# Mynd_UI.net
KiCad netlist of a schematic drawn in Altium Designer
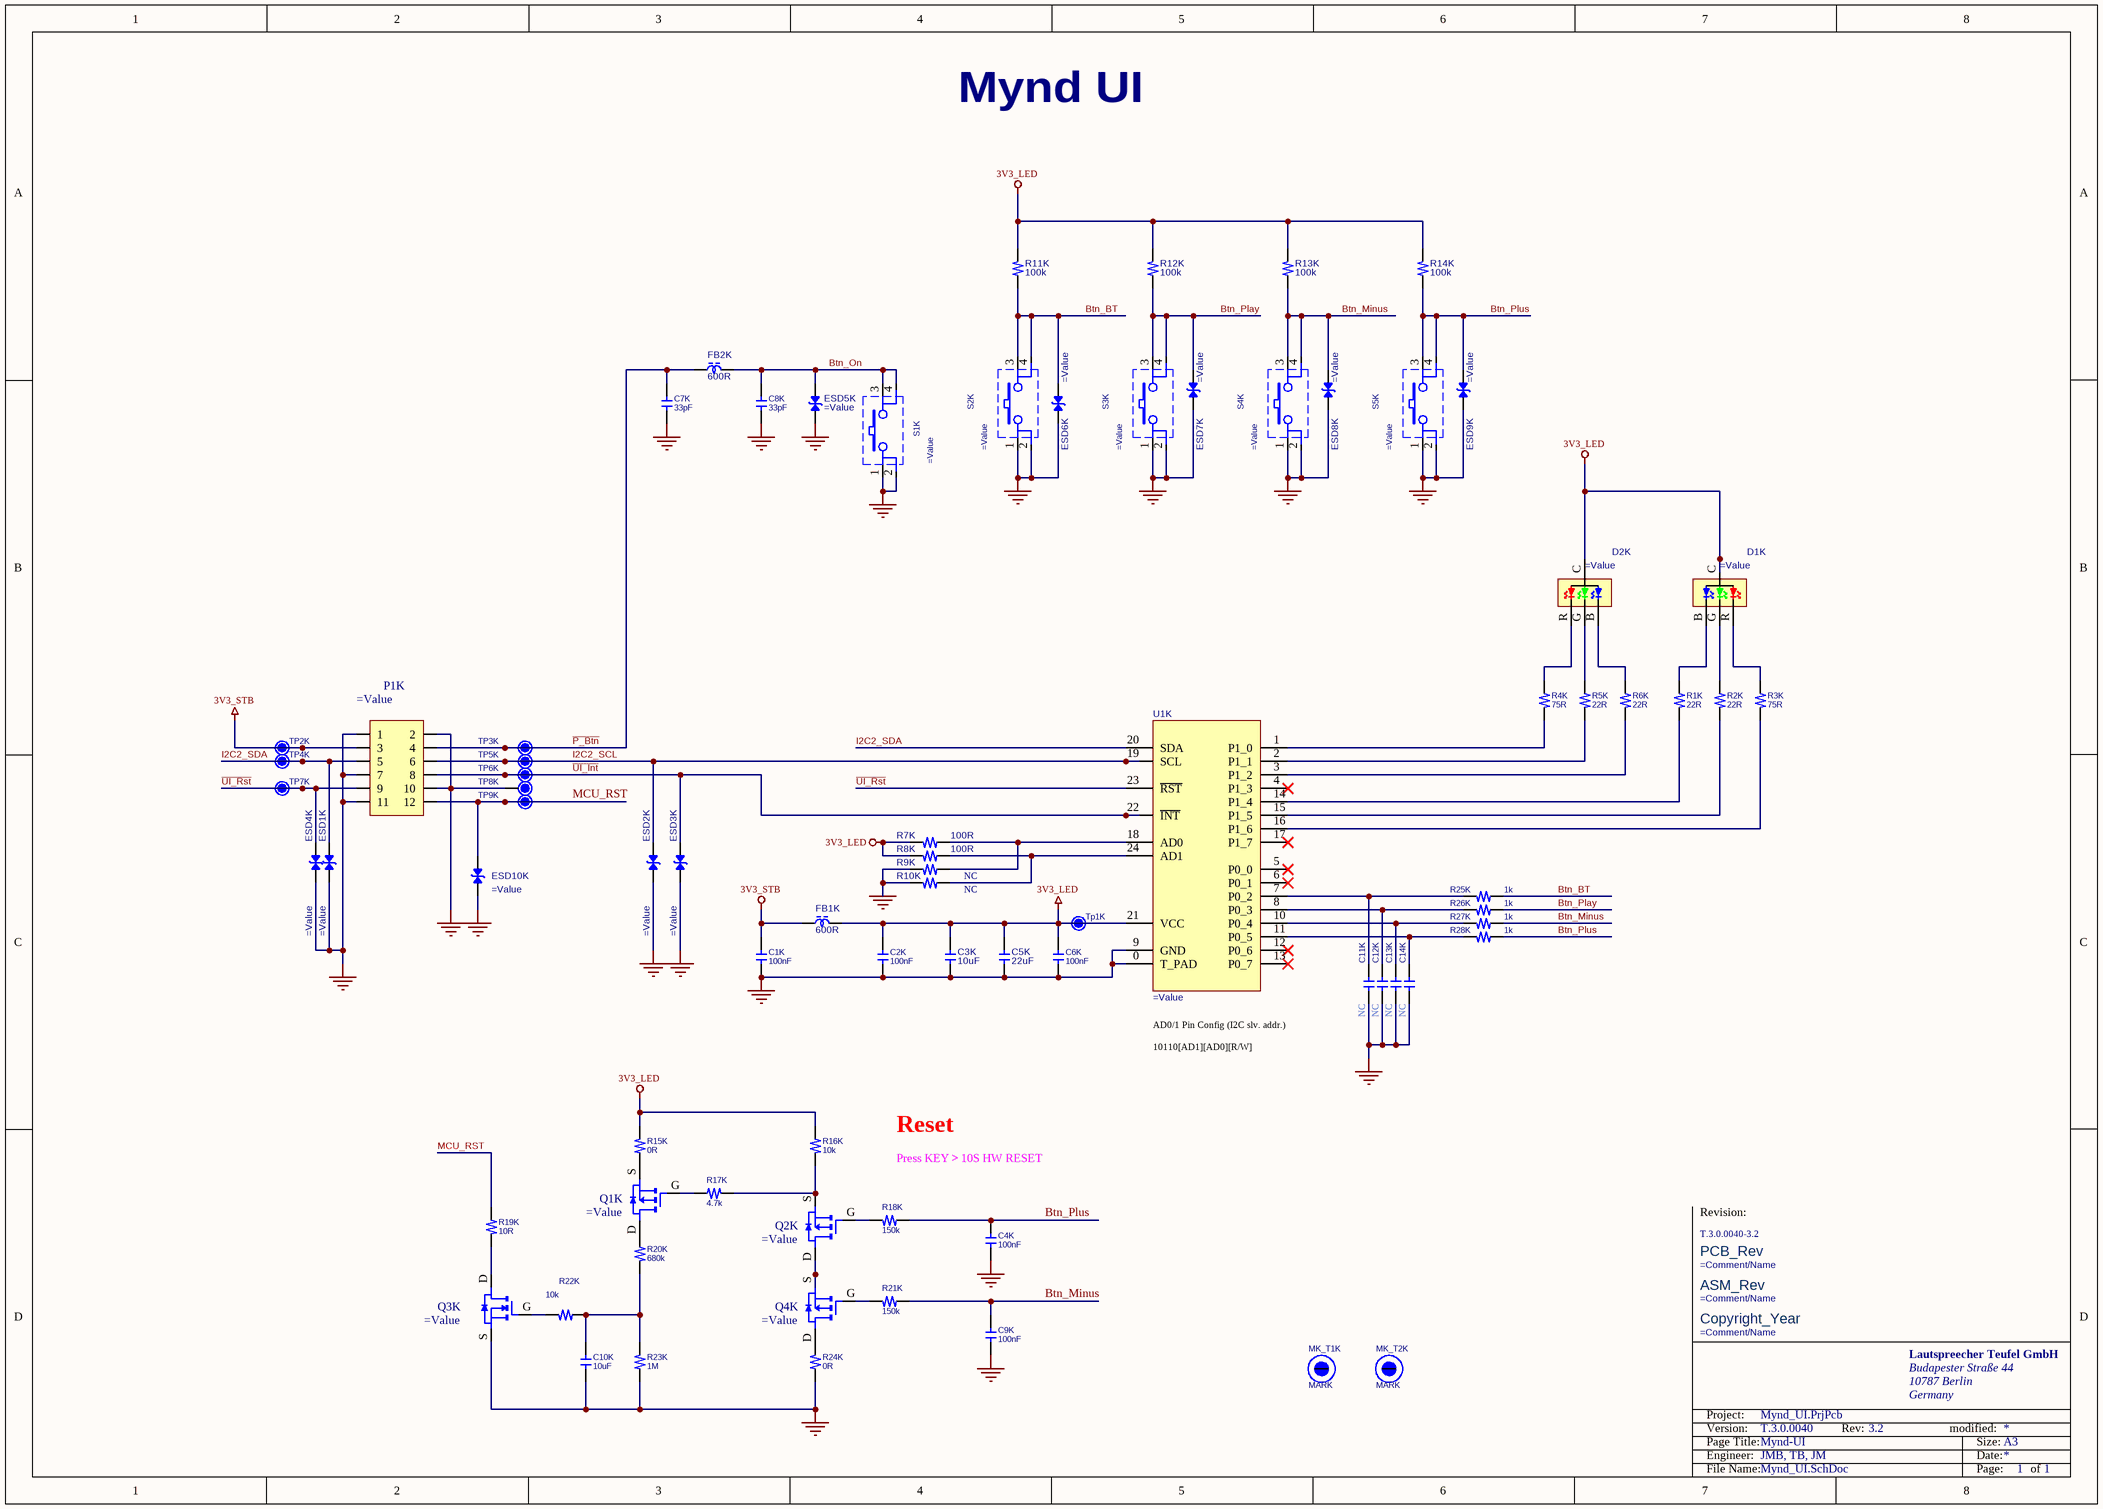
[diagram p0: Mynd_UI.SchDoc]

(export (version "E")
  (design (tool "Eeschema 10.0.6"))
  (components
    (comp (ref "C1K")
      (value "100nF")
      (footprint "C0603X100")
      (description "GPHF SMD M CAP 100nF 16V ±10%  0603 X7R")
      (fields (field (name "MANUFACTURER") "Multi-Sourced") (field (name "TOLERANCE") "±10%"))
      (libsource (lib "altium-import") (part "root_3_CAP1_"))
    )
    (comp (ref "C2K")
      (value "100nF")
      (footprint "C0603X100")
      (description "GPHF SMD M CAP 100nF 16V ±10%  0603 X7R")
      (fields (field (name "MANUFACTURER") "Multi-Sourced") (field (name "TOLERANCE") "±10%"))
      (libsource (lib "altium-import") (part "root_3_CAP1_"))
    )
    (comp (ref "C3K")
      (value "10uF")
      (footprint "C0805_145")
      (description "PSHF SMD M CAP 10uF 16V ±10% 0805 X7R")
      (fields (field (name "MANUFACTURER") "Multi-Sourced") (field (name "TOLERANCE") "±10% 0805"))
      (libsource (lib "altium-import") (part "root_3_CAP1_"))
    )
    (comp (ref "C4K")
      (value "100nF")
      (footprint "C0603X100")
      (description "GPHF SMD M CAP 100nF 16V ±10%  0603 X7R")
      (fields (field (name "MANUFACTURER") "Multi-Sourced") (field (name "VOLTAGE") "16V"))
      (libsource (lib "altium-import") (part "root_3_mirrored_CAP1_"))
    )
    (comp (ref "C5K")
      (value "22uF")
      (footprint "C1206")
      (description "PSHF SMD M CAP 22uF 16V ±10% 1206 X5R")
      (fields (field (name "MANUFACTURER") "Multi-Sourced") (field (name "TOLERANCE") "±10%"))
      (libsource (lib "altium-import") (part "root_1_mirrored_CAP1_"))
    )
    (comp (ref "C6K")
      (value "100nF")
      (footprint "C0603X100")
      (description "GPHF SMD M CAP 100nF 16V ±10%  0603 X7R")
      (fields (field (name "MANUFACTURER") "Multi-Sourced") (field (name "TOLERANCE") "±10%"))
      (libsource (lib "altium-import") (part "root_1_CAP1_"))
    )
    (comp (ref "C7K")
      (value "33pF")
      (footprint "C0603X80")
      (description "PSHF SMD M CAP 33pF 50V ±5% 0603 NPO")
      (fields (field (name "MANUFACTURER") "Multi-Sourced") (field (name "TOLERANCE") "±5%"))
      (libsource (lib "altium-import") (part "root_3_CAP1_"))
    )
    (comp (ref "C8K")
      (value "33pF")
      (footprint "C0603X80")
      (description "PSHF SMD M CAP 33pF 50V ±5% 0603 NPO")
      (fields (field (name "MANUFACTURER") "Multi-Sourced") (field (name "TOLERANCE") "±5%"))
      (libsource (lib "altium-import") (part "root_3_CAP1_"))
    )
    (comp (ref "C9K")
      (value "100nF")
      (footprint "C0603X100")
      (description "GPHF SMD M CAP 100nF 16V ±10%  0603 X7R")
      (fields (field (name "MANUFACTURER") "Multi-Sourced") (field (name "VOLTAGE") "16V"))
      (libsource (lib "altium-import") (part "root_3_mirrored_CAP1_"))
    )
    (comp (ref "C10K")
      (value "10uF")
      (footprint "C0805_145")
      (description "PSHF SMD M CAP 10uF 10V ±10% 0805 X5R")
      (fields (field (name "MANUFACTURER") "Multi-Sourced") (field (name "VOLTAGE") "10V"))
      (libsource (lib "altium-import") (part "root_3_mirrored_CAP1_"))
    )
    (comp (ref "C11K")
      (value "NC")
      (footprint "C0603X100")
      (description "GPHF SMD M CAP 100nF 16V ±10%  0603 X7R")
      (fields (field (name "MANUFACTURER") "Multi-Sourced") (field (name "TOLERANCE") "±10%"))
      (libsource (lib "altium-import") (part "root_3_CAP1_"))
    )
    (comp (ref "C12K")
      (value "NC")
      (footprint "C0603X100")
      (description "GPHF SMD M CAP 100nF 16V ±10%  0603 X7R")
      (fields (field (name "MANUFACTURER") "Multi-Sourced") (field (name "TOLERANCE") "±10%"))
      (libsource (lib "altium-import") (part "root_3_CAP1_"))
    )
    (comp (ref "C13K")
      (value "NC")
      (footprint "C0603X100")
      (description "GPHF SMD M CAP 100nF 16V ±10%  0603 X7R")
      (fields (field (name "MANUFACTURER") "Multi-Sourced") (field (name "TOLERANCE") "±10%"))
      (libsource (lib "altium-import") (part "root_3_CAP1_"))
    )
    (comp (ref "C14K")
      (value "NC")
      (footprint "C0603X100")
      (description "GPHF SMD M CAP 100nF 16V ±10%  0603 X7R")
      (fields (field (name "MANUFACTURER") "Multi-Sourced") (field (name "TOLERANCE") "±10%"))
      (libsource (lib "altium-import") (part "root_3_CAP1_"))
    )
    (comp (ref "D1K")
      (value "~")
      (footprint "LED_SMD_F_T_160X80X60")
      (description "SMD LED 4P 30mA RED&GN&BU")
      (fields (field (name "MANUFACTURER") "MINGSHUO") (field (name "PART_NUMBER") "JH-CRGBB06GTP014"))
      (libsource (lib "altium-import") (part "root_3_LED_RGB_4P_"))
    )
    (comp (ref "D2K")
      (value "~")
      (footprint "LED_SMD_F_T_160X80X60")
      (description "SMD LED 4P 30mA RED&GN&BU")
      (fields (field (name "MANUFACTURER") "MINGSHUO") (field (name "PART_NUMBER") "JH-CRGBB06GTP014"))
      (libsource (lib "altium-import") (part "root_3_mirrored_LED_RGB_4P_"))
    )
    (comp (ref "ESD1K")
      (value "~")
      (footprint "DFN2_100X60X50_65")
      (description "SMD TVS 2P 5.5 DFN1006 CESD0501CU CTE")
      (fields (field (name "MANUFACTURER") "CTE") (field (name "PART_NUMBER") "CESD0501CU"))
      (libsource (lib "altium-import") (part "root_1_DIODE_BID_ESD2_"))
    )
    (comp (ref "ESD2K")
      (value "~")
      (footprint "DFN2_100X60X50_65")
      (description "SMD TVS 2P 5.5 DFN1006 CESD0501CU CTE")
      (fields (field (name "MANUFACTURER") "CTE") (field (name "PART_NUMBER") "CESD0501CU"))
      (libsource (lib "altium-import") (part "root_1_DIODE_BID_ESD2_"))
    )
    (comp (ref "ESD3K")
      (value "~")
      (footprint "DFN2_100X60X50_65")
      (description "SMD TVS 2P 5.5 DFN1006 CESD0501CU CTE")
      (fields (field (name "MANUFACTURER") "CTE") (field (name "PART_NUMBER") "CESD0501CU"))
      (libsource (lib "altium-import") (part "root_1_DIODE_BID_ESD2_"))
    )
    (comp (ref "ESD4K")
      (value "~")
      (footprint "DFN2_100X60X50_65")
      (description "SMD TVS 2P 5.5 DFN1006 CESD0501CU CTE")
      (fields (field (name "MANUFACTURER") "CTE") (field (name "PART_NUMBER") "CESD0501CU"))
      (libsource (lib "altium-import") (part "root_1_DIODE_BID_ESD2_"))
    )
    (comp (ref "ESD5K")
      (value "~")
      (footprint "DFN2_100X60X50_65")
      (description "SMD TVS 2P DFN1006 BDFN2C121V")
      (fields (field (name "MANUFACTURER") "[]") (field (name "PART_NUMBER") "BDFN2C121V"))
      (libsource (lib "altium-import") (part "root_1_DIODE_BID_ESD2_"))
    )
    (comp (ref "ESD6K")
      (value "~")
      (footprint "DFN2_100X60X50_65")
      (description "SMD TVS 2P 5.5 DFN1006 CESD0501CU CTE")
      (fields (field (name "MANUFACTURER") "CTE") (field (name "PART_NUMBER") "CESD0501CU"))
      (libsource (lib "altium-import") (part "root_1_DIODE_BID_ESD2_"))
    )
    (comp (ref "ESD7K")
      (value "~")
      (footprint "DFN2_100X60X50_65")
      (description "SMD TVS 2P 5.5 DFN1006 CESD0501CU CTE")
      (fields (field (name "MANUFACTURER") "CTE") (field (name "PART_NUMBER") "CESD0501CU"))
      (libsource (lib "altium-import") (part "root_1_DIODE_BID_ESD2_"))
    )
    (comp (ref "ESD8K")
      (value "~")
      (footprint "DFN2_100X60X50_65")
      (description "SMD TVS 2P 5.5 DFN1006 CESD0501CU CTE")
      (fields (field (name "MANUFACTURER") "CTE") (field (name "PART_NUMBER") "CESD0501CU"))
      (libsource (lib "altium-import") (part "root_1_DIODE_BID_ESD2_"))
    )
    (comp (ref "ESD9K")
      (value "~")
      (footprint "DFN2_100X60X50_65")
      (description "SMD TVS 2P 5.5 DFN1006 CESD0501CU CTE")
      (fields (field (name "MANUFACTURER") "CTE") (field (name "PART_NUMBER") "CESD0501CU"))
      (libsource (lib "altium-import") (part "root_1_DIODE_BID_ESD2_"))
    )
    (comp (ref "ESD10K")
      (value "~")
      (footprint "DFN2_100X60X50_65")
      (description "SMD TVS 2P 5.5 DFN1006 CESD0501CU CTE")
      (fields (field (name "MANUFACTURER") "CTE") (field (name "PART_NUMBER") "CESD0501CU"))
      (libsource (lib "altium-import") (part "root_1_DIODE_BID_ESD2_"))
    )
    (comp (ref "FB1K")
      (value "600R")
      (footprint "L0603")
      (description "PS SMD FERRITE BEAD 600OHM 25% 0603")
      (fields (field (name "MANUFACTURER") "[TSA]") (field (name "TOLERANCE") "1:25%"))
      (libsource (lib "altium-import") (part "root_0_mirrored_Bead1_"))
    )
    (comp (ref "FB2K")
      (value "600R")
      (footprint "L0603")
      (description "PS SMD FERRITE BEAD 600OHM 25% 0603")
      (fields (field (name "MANUFACTURER") "[TSA]") (field (name "TOLERANCE") "1:25%"))
      (libsource (lib "altium-import") (part "root_0_Bead1_"))
    )
    (comp (ref "MK_T1K")
      (value "MARK")
      (footprint "MARK")
      (description "MARK DOT")
      (libsource (lib "altium-import") (part "root_0_MARK_"))
    )
    (comp (ref "MK_T2K")
      (value "MARK")
      (footprint "MARK")
      (description "MARK DOT")
      (libsource (lib "altium-import") (part "root_0_MARK_"))
    )
    (comp (ref "P1K")
      (value "~")
      (footprint "WB200AL_2x6P")
      (description "SMD WTB CONNECTOR 12P P2.0mm TIN")
      (fields (field (name "MANUFACTURER") "MINGHENG") (field (name "PART_NUMBER") "WB200AL-12"))
      (libsource (lib "altium-import") (part "root_0_CON 2X6P_"))
    )
    (comp (ref "Q1K")
      (value "~")
      (footprint "SOT23-GSD")
      (description "GPHF SMD FET 3P -30V SOT-23 CJ3401 CJ")
      (fields (field (name "MANUFACTURER") "CJ") (field (name "PART_NUMBER") "CJ3401"))
      (libsource (lib "altium-import") (part "root_2_P-MOS1_"))
    )
    (comp (ref "Q2K")
      (value "~")
      (footprint "SOT23-GSD")
      (description "GPHF SMD FET 3P -30V SOT-23 CJ3401 CJ")
      (fields (field (name "MANUFACTURER") "CJ") (field (name "PART_NUMBER") "CJ3401"))
      (libsource (lib "altium-import") (part "root_2_P-MOS1_"))
    )
    (comp (ref "Q3K")
      (value "~")
      (footprint "SOT23-GSD")
      (description "GP SMD FET 3P SOT23 2N7002K CTE")
      (fields (field (name "MANUFACTURER") "CTE") (field (name "PART_NUMBER") "2N7002K"))
      (libsource (lib "altium-import") (part "root_0_mirrored_N-MOS1_"))
    )
    (comp (ref "Q4K")
      (value "~")
      (footprint "SOT23-GSD")
      (description "GPHF SMD FET 3P -30V SOT-23 CJ3401 CJ")
      (fields (field (name "MANUFACTURER") "CJ") (field (name "PART_NUMBER") "CJ3401"))
      (libsource (lib "altium-import") (part "root_2_P-MOS1_"))
    )
    (comp (ref "R1K")
      (value "22R")
      (footprint "R0603")
      (description "PS SMD RES. 22OHM 1/10W 5% 0603")
      (fields (field (name "TOLERANCE") "5%") (field (name "MANUFACTURER") "Multi-Sourced"))
      (libsource (lib "altium-import") (part "root_3_mirrored_RES1_"))
    )
    (comp (ref "R2K")
      (value "22R")
      (footprint "R0603")
      (description "PS SMD RES. 22OHM 1/10W 5% 0603")
      (fields (field (name "TOLERANCE") "5%") (field (name "MANUFACTURER") "Multi-Sourced"))
      (libsource (lib "altium-import") (part "root_3_mirrored_RES1_"))
    )
    (comp (ref "R3K")
      (value "75R")
      (footprint "R0603")
      (description "PS SMD RES. 75OHM 1/10W 1% 0603")
      (fields (field (name "TOLERANCE") "1%") (field (name "MANUFACTURER") "Multi-Sourced"))
      (libsource (lib "altium-import") (part "root_3_mirrored_RES1_"))
    )
    (comp (ref "R4K")
      (value "75R")
      (footprint "R0603")
      (description "PS SMD RES. 75OHM 1/10W 1% 0603")
      (fields (field (name "TOLERANCE") "1%") (field (name "MANUFACTURER") "Multi-Sourced"))
      (libsource (lib "altium-import") (part "root_3_mirrored_RES1_"))
    )
    (comp (ref "R5K")
      (value "22R")
      (footprint "R0603")
      (description "PS SMD RES. 22OHM 1/10W 5% 0603")
      (fields (field (name "TOLERANCE") "5%") (field (name "MANUFACTURER") "Multi-Sourced"))
      (libsource (lib "altium-import") (part "root_3_mirrored_RES1_"))
    )
    (comp (ref "R6K")
      (value "22R")
      (footprint "R0603")
      (description "PS SMD RES. 22OHM 1/10W 5% 0603")
      (fields (field (name "TOLERANCE") "5%") (field (name "MANUFACTURER") "Multi-Sourced"))
      (libsource (lib "altium-import") (part "root_3_mirrored_RES1_"))
    )
    (comp (ref "R7K")
      (value "100R")
      (footprint "R0603")
      (description "PS SMD RES. 100OHM 1/10W 1% 0603")
      (fields (field (name "TOLERANCE") "1%") (field (name "MANUFACTURER") "Multi-Sourced"))
      (libsource (lib "altium-import") (part "root_0_mirrored_RES1_"))
    )
    (comp (ref "R8K")
      (value "100R")
      (footprint "R0603")
      (description "PS SMD RES. 100OHM 1/10W 1% 0603")
      (fields (field (name "TOLERANCE") "1%") (field (name "MANUFACTURER") "Multi-Sourced"))
      (libsource (lib "altium-import") (part "root_0_mirrored_RES1_"))
    )
    (comp (ref "R9K")
      (value "10k")
      (footprint "R0603")
      (description "PS SMD RES. 10KOHM 1/10W 1% 0603")
      (fields (field (name "TOLERANCE") "1%") (field (name "MANUFACTURER") "Multi-Sourced"))
      (libsource (lib "altium-import") (part "root_0_mirrored_RES1_"))
    )
    (comp (ref "R10K")
      (value "10k")
      (footprint "R0603")
      (description "PS SMD RES. 10KOHM 1/10W 1% 0603")
      (fields (field (name "TOLERANCE") "1%") (field (name "MANUFACTURER") "Multi-Sourced"))
      (libsource (lib "altium-import") (part "root_0_mirrored_RES1_"))
    )
    (comp (ref "R11K")
      (value "100k")
      (footprint "R0603")
      (description "PS SMD RES. 100KOHM 1/10W 1% 0603")
      (fields (field (name "TOLERANCE") "1%") (field (name "MANUFACTURER") "Multi-Sourced"))
      (libsource (lib "altium-import") (part "root_3_RES1_"))
    )
    (comp (ref "R12K")
      (value "100k")
      (footprint "R0603")
      (description "PS SMD RES. 100KOHM 1/10W 1% 0603")
      (fields (field (name "TOLERANCE") "1%") (field (name "MANUFACTURER") "Multi-Sourced"))
      (libsource (lib "altium-import") (part "root_3_RES1_"))
    )
    (comp (ref "R13K")
      (value "100k")
      (footprint "R0603")
      (description "PS SMD RES. 100KOHM 1/10W 1% 0603")
      (fields (field (name "TOLERANCE") "1%") (field (name "MANUFACTURER") "Multi-Sourced"))
      (libsource (lib "altium-import") (part "root_3_RES1_"))
    )
    (comp (ref "R14K")
      (value "100k")
      (footprint "R0603")
      (description "PS SMD RES. 100KOHM 1/10W 1% 0603")
      (fields (field (name "TOLERANCE") "1%") (field (name "MANUFACTURER") "Multi-Sourced"))
      (libsource (lib "altium-import") (part "root_3_RES1_"))
    )
    (comp (ref "R15K")
      (value "0R")
      (footprint "R0603")
      (description "GPHF SMD RES. 0OHM 1/10W 5% 0603")
      (fields (field (name "MANUFACTURER") "Multi-Sourced") (field (name "TOLERANCE") "5%"))
      (libsource (lib "altium-import") (part "root_3_RES1_"))
    )
    (comp (ref "R16K")
      (value "10k")
      (footprint "R0603")
      (description "GPHF SMD RES. 10KOHM 1/10W 5% 0603")
      (fields (field (name "MANUFACTURER") "Multi-Sourced") (field (name "TOLERANCE") "5%"))
      (libsource (lib "altium-import") (part "root_1_RES1_"))
    )
    (comp (ref "R17K")
      (value "4.7k")
      (footprint "R0603")
      (description "GPHF SMD RES. 4.7KOHM 1/10W 5% 0603")
      (fields (field (name "MANUFACTURER") "Multi-Sourced") (field (name "TOLERANCE") "5%"))
      (libsource (lib "altium-import") (part "root_2_RES1_"))
    )
    (comp (ref "R18K")
      (value "150k")
      (footprint "R0603")
      (description "GPHF SMD RES. 150KOHM 1/10W 5% 0603")
      (fields (field (name "MANUFACTURER") "Multi-Sourced") (field (name "TOLERANCE") "5%"))
      (libsource (lib "altium-import") (part "root_0_mirrored_RES1_"))
    )
    (comp (ref "R19K")
      (value "10R")
      (footprint "R0603")
      (description "GPHF SMD RES. 10OHM 1/10W 1% 0603")
      (fields (field (name "MANUFACTURER") "Multi-Sourced") (field (name "TOLERANCE") "1%"))
      (libsource (lib "altium-import") (part "root_3_mirrored_RES1_"))
    )
    (comp (ref "R20K")
      (value "680k")
      (footprint "R0603")
      (description "GPHF SMD RES. 680KOHM 1/10W 5% 0603")
      (fields (field (name "MANUFACTURER") "Multi-Sourced") (field (name "TOLERANCE") "5%"))
      (libsource (lib "altium-import") (part "root_3_mirrored_RES1_"))
    )
    (comp (ref "R21K")
      (value "150k")
      (footprint "R0603")
      (description "GPHF SMD RES. 150KOHM 1/10W 5% 0603")
      (fields (field (name "MANUFACTURER") "Multi-Sourced") (field (name "TOLERANCE") "5%"))
      (libsource (lib "altium-import") (part "root_0_mirrored_RES1_"))
    )
    (comp (ref "R22K")
      (value "10k")
      (footprint "R0603")
      (description "GPHF SMD RES. 10KOHM 1/10W 5% 0603")
      (fields (field (name "MANUFACTURER") "Multi-Sourced") (field (name "TOLERANCE") "5%"))
      (libsource (lib "altium-import") (part "root_0_mirrored_RES1_"))
    )
    (comp (ref "R23K")
      (value "1M")
      (footprint "R0603")
      (description "GPHF $ SMD RES. 1MOHM 1/10W 5% 0603")
      (fields (field (name "MANUFACTURER") "Multi-Sourced") (field (name "TOLERANCE") "5%"))
      (libsource (lib "altium-import") (part "root_1_mirrored_RES1_"))
    )
    (comp (ref "R24K")
      (value "0R")
      (footprint "R0603")
      (description "GPHF SMD RES. 0OHM 1/10W 5% 0603")
      (fields (field (name "MANUFACTURER") "Multi-Sourced") (field (name "TOLERANCE") "5%"))
      (libsource (lib "altium-import") (part "root_1_mirrored_RES1_"))
    )
    (comp (ref "R25K")
      (value "1k")
      (footprint "R0603")
      (description "GPHF SMD RES. 1KOHM 1/10W 1% 0603")
      (fields (field (name "MANUFACTURER") "Multi-Sourced") (field (name "TOLERANCE") "1%"))
      (libsource (lib "altium-import") (part "root_0_RES1_"))
    )
    (comp (ref "R26K")
      (value "1k")
      (footprint "R0603")
      (description "GPHF SMD RES. 1KOHM 1/10W 1% 0603")
      (fields (field (name "MANUFACTURER") "Multi-Sourced") (field (name "TOLERANCE") "1%"))
      (libsource (lib "altium-import") (part "root_0_RES1_"))
    )
    (comp (ref "R27K")
      (value "1k")
      (footprint "R0603")
      (description "GPHF SMD RES. 1KOHM 1/10W 1% 0603")
      (fields (field (name "MANUFACTURER") "Multi-Sourced") (field (name "TOLERANCE") "1%"))
      (libsource (lib "altium-import") (part "root_0_RES1_"))
    )
    (comp (ref "R28K")
      (value "1k")
      (footprint "R0603")
      (description "GPHF SMD RES. 1KOHM 1/10W 1% 0603")
      (fields (field (name "MANUFACTURER") "Multi-Sourced") (field (name "TOLERANCE") "1%"))
      (libsource (lib "altium-import") (part "root_0_RES1_"))
    )
    (comp (ref "S1K")
      (value "~")
      (footprint "TACT_SW_SMD_52X52X15")
      (description "SMD SWITCH 4P TC-1316A-H1.5-180G")
      (fields (field (name "MANUFACTURER") "[MINGHENG]") (field (name "PART_NUMBER") "TC-1316A-H1.5-180GF"))
      (libsource (lib "altium-import") (part "root_1_TACT_SW_A_"))
    )
    (comp (ref "S2K")
      (value "~")
      (footprint "TACT_SW_SMD_52X52X15")
      (description "SMD SWITCH 4P TC-1316A-H1.5-180G")
      (fields (field (name "MANUFACTURER") "[MINGHENG]") (field (name "PART_NUMBER") "TC-1316A-H1.5-180GF"))
      (libsource (lib "altium-import") (part "root_1_TACT_SW_A_"))
    )
    (comp (ref "S3K")
      (value "~")
      (footprint "TACT_SW_SMD_52X52X15")
      (description "SMD SWITCH 4P TC-1316A-H1.5-180G")
      (fields (field (name "MANUFACTURER") "[MINGHENG]") (field (name "PART_NUMBER") "TC-1316A-H1.5-180GF"))
      (libsource (lib "altium-import") (part "root_1_TACT_SW_A_"))
    )
    (comp (ref "S4K")
      (value "~")
      (footprint "TACT_SW_SMD_52X52X15")
      (description "SMD SWITCH 4P TC-1316A-H1.5-180G")
      (fields (field (name "MANUFACTURER") "[MINGHENG]") (field (name "PART_NUMBER") "TC-1316A-H1.5-180GF"))
      (libsource (lib "altium-import") (part "root_1_TACT_SW_A_"))
    )
    (comp (ref "S5K")
      (value "~")
      (footprint "TACT_SW_SMD_52X52X15")
      (description "SMD SWITCH 4P TC-1316A-H1.5-180G")
      (fields (field (name "MANUFACTURER") "[MINGHENG]") (field (name "PART_NUMBER") "TC-1316A-H1.5-180GF"))
      (libsource (lib "altium-import") (part "root_1_TACT_SW_A_"))
    )
    (comp (ref "Teufel_ASM_Label1K")
      (value "~")
      (footprint "Teufel_ASM_Rev")
      (description "Teufel_ASM_Rev")
      (libsource (lib "altium-import") (part "root_0_Teufel_ASM_Label_"))
    )
    (comp (ref "Teufel_Copyright1K")
      (value "~")
      (footprint "TEUFEL_COPYRIGHT")
      (description "Teufel_Copyright_Year")
      (libsource (lib "altium-import") (part "root_0_Teufel_Copyright_"))
    )
    (comp (ref "Teufel_PCB_Label1K")
      (value "~")
      (footprint "Teufel_PCB_Rev")
      (description "Teufel_PCB_Label")
      (libsource (lib "altium-import") (part "root_0_Teufel_PCB_Label_"))
    )
    (comp (ref "Teufel_PCB_Logo1K")
      (value "-3.2")
      (footprint "Teufel_NoLogo")
      (description "Teufel PCB NoLogo")
      (libsource (lib "altium-import") (part "root_0_Teufel NoLogo_"))
    )
    (comp (ref "Tp1K")
      (value "TP_T_60_40")
      (footprint "TP_T_60_40")
      (description "Test Point")
      (libsource (lib "altium-import") (part "root_0_TP_"))
    )
    (comp (ref "TP2K")
      (value "TP12")
      (footprint "TP120")
      (description "Test Point")
      (libsource (lib "altium-import") (part "root_0_mirrored_TP_"))
    )
    (comp (ref "TP3K")
      (value "TP12")
      (footprint "TP120")
      (description "Test Point")
      (libsource (lib "altium-import") (part "root_0_TP_"))
    )
    (comp (ref "TP4K")
      (value "TP12")
      (footprint "TP120")
      (description "Test Point")
      (libsource (lib "altium-import") (part "root_0_mirrored_TP_"))
    )
    (comp (ref "TP5K")
      (value "TP12")
      (footprint "TP120")
      (description "Test Point")
      (libsource (lib "altium-import") (part "root_0_TP_"))
    )
    (comp (ref "TP6K")
      (value "TP12")
      (footprint "TP120")
      (description "Test Point")
      (libsource (lib "altium-import") (part "root_0_TP_"))
    )
    (comp (ref "TP7K")
      (value "TP12")
      (footprint "TP120")
      (description "Test Point")
      (libsource (lib "altium-import") (part "root_0_mirrored_TP_"))
    )
    (comp (ref "TP8K")
      (value "TP12")
      (footprint "TP120")
      (description "Test Point")
      (libsource (lib "altium-import") (part "root_0_TP_"))
    )
    (comp (ref "TP9K")
      (value "TP12")
      (footprint "TP120")
      (description "Test Point")
      (libsource (lib "altium-import") (part "root_0_TP_"))
    )
    (comp (ref "U1K")
      (value "~")
      (footprint "QFN24_400X400X100_50_P270X270")
      (description "GP SMD IC 24P TQFN AW9523BTQR AWINIC")
      (fields (field (name "MANUFACTURER") "AWINIC") (field (name "PART_NUMBER") "AW9523BTQR"))
      (libsource (lib "altium-import") (part "root_0_AW9523B_"))
    )
  )
  (nets
    (net (code "1") (name "/Btn_BT") (class "Default")
      (node (ref "ESD6K") (pin "2") (pinfunction "2_2") (pintype "passive"))
      (node (ref "R11K") (pin "2") (pinfunction "2_2") (pintype "passive"))
      (node (ref "R25K") (pin "2") (pinfunction "2_2") (pintype "passive"))
      (node (ref "S2K") (pin "3") (pinfunction "3_3") (pintype "passive"))
      (node (ref "S2K") (pin "4") (pinfunction "4_4") (pintype "passive"))
    )
    (net (code "2") (name "/Btn_Minus") (class "Default")
      (node (ref "C9K") (pin "1") (pinfunction "1_1") (pintype "passive"))
      (node (ref "ESD8K") (pin "2") (pinfunction "2_2") (pintype "passive"))
      (node (ref "R13K") (pin "2") (pinfunction "2_2") (pintype "passive"))
      (node (ref "R21K") (pin "1") (pinfunction "1_1") (pintype "passive"))
      (node (ref "R27K") (pin "2") (pinfunction "2_2") (pintype "passive"))
      (node (ref "S4K") (pin "3") (pinfunction "3_3") (pintype "passive"))
      (node (ref "S4K") (pin "4") (pinfunction "4_4") (pintype "passive"))
    )
    (net (code "3") (name "/Btn_On") (class "Default")
      (node (ref "C8K") (pin "1") (pinfunction "1_1") (pintype "passive"))
      (node (ref "ESD5K") (pin "2") (pinfunction "2_2") (pintype "passive"))
      (node (ref "FB2K") (pin "2") (pinfunction "2_2") (pintype "passive"))
      (node (ref "S1K") (pin "3") (pinfunction "3_3") (pintype "passive"))
      (node (ref "S1K") (pin "4") (pinfunction "4_4") (pintype "passive"))
    )
    (net (code "4") (name "/Btn_Play") (class "Default")
      (node (ref "ESD7K") (pin "2") (pinfunction "2_2") (pintype "passive"))
      (node (ref "R12K") (pin "2") (pinfunction "2_2") (pintype "passive"))
      (node (ref "R26K") (pin "2") (pinfunction "2_2") (pintype "passive"))
      (node (ref "S3K") (pin "3") (pinfunction "3_3") (pintype "passive"))
      (node (ref "S3K") (pin "4") (pinfunction "4_4") (pintype "passive"))
    )
    (net (code "5") (name "/Btn_Plus") (class "Default")
      (node (ref "C4K") (pin "1") (pinfunction "1_1") (pintype "passive"))
      (node (ref "ESD9K") (pin "2") (pinfunction "2_2") (pintype "passive"))
      (node (ref "R14K") (pin "2") (pinfunction "2_2") (pintype "passive"))
      (node (ref "R18K") (pin "1") (pinfunction "1_1") (pintype "passive"))
      (node (ref "R28K") (pin "2") (pinfunction "2_2") (pintype "passive"))
      (node (ref "S5K") (pin "3") (pinfunction "3_3") (pintype "passive"))
      (node (ref "S5K") (pin "4") (pinfunction "4_4") (pintype "passive"))
    )
    (net (code "6") (name "/I2C2_SCL") (class "Default")
      (node (ref "ESD2K") (pin "2") (pinfunction "2_2") (pintype "passive"))
      (node (ref "P1K") (pin "6") (pinfunction "6_6") (pintype "passive"))
      (node (ref "TP5K") (pin "1") (pinfunction "1_1") (pintype "passive"))
      (node (ref "U1K") (pin "19") (pinfunction "SCL_19") (pintype "passive"))
    )
    (net (code "7") (name "/I2C2_SDA") (class "Default")
      (node (ref "ESD1K") (pin "2") (pinfunction "2_2") (pintype "passive"))
      (node (ref "P1K") (pin "5") (pinfunction "5_5") (pintype "passive"))
      (node (ref "TP4K") (pin "1") (pinfunction "1_1") (pintype "passive"))
      (node (ref "U1K") (pin "20") (pinfunction "SDA_20") (pintype "passive"))
    )
    (net (code "8") (name "/MCU_RST") (class "Default")
      (node (ref "ESD10K") (pin "2") (pinfunction "2_2") (pintype "passive"))
      (node (ref "P1K") (pin "12") (pinfunction "12_12") (pintype "passive"))
      (node (ref "R19K") (pin "1") (pinfunction "1_1") (pintype "passive"))
      (node (ref "TP9K") (pin "1") (pinfunction "1_1") (pintype "passive"))
    )
    (net (code "9") (name "/P_Btn") (class "Default")
      (node (ref "C7K") (pin "1") (pinfunction "1_1") (pintype "passive"))
      (node (ref "FB2K") (pin "1") (pinfunction "1_1") (pintype "passive"))
      (node (ref "P1K") (pin "4") (pinfunction "4_4") (pintype "passive"))
      (node (ref "TP3K") (pin "1") (pinfunction "1_1") (pintype "passive"))
    )
    (net (code "10") (name "/UI_Int") (class "Default")
      (node (ref "ESD3K") (pin "2") (pinfunction "2_2") (pintype "passive"))
      (node (ref "P1K") (pin "8") (pinfunction "8_8") (pintype "passive"))
      (node (ref "TP6K") (pin "1") (pinfunction "1_1") (pintype "passive"))
      (node (ref "U1K") (pin "22") (pinfunction "~{INT}_22") (pintype "passive"))
    )
    (net (code "11") (name "/UI_Rst") (class "Default")
      (node (ref "ESD4K") (pin "2") (pinfunction "2_2") (pintype "passive"))
      (node (ref "P1K") (pin "9") (pinfunction "9_9") (pintype "passive"))
      (node (ref "TP7K") (pin "1") (pinfunction "1_1") (pintype "passive"))
      (node (ref "U1K") (pin "23") (pinfunction "~{RST}_23") (pintype "passive"))
    )
    (net (code "12") (name "3V3_LED") (class "Default")
      (node (ref "C2K") (pin "1") (pinfunction "1_1") (pintype "passive"))
      (node (ref "C3K") (pin "1") (pinfunction "1_1") (pintype "passive"))
      (node (ref "C5K") (pin "2") (pinfunction "2_2") (pintype "passive"))
      (node (ref "C6K") (pin "2") (pinfunction "2_2") (pintype "passive"))
      (node (ref "D1K") (pin "C") (pinfunction "C_C") (pintype "passive"))
      (node (ref "D2K") (pin "C") (pinfunction "C_C") (pintype "passive"))
      (node (ref "FB1K") (pin "1") (pinfunction "1_1") (pintype "passive"))
      (node (ref "R11K") (pin "1") (pinfunction "1_1") (pintype "passive"))
      (node (ref "R12K") (pin "1") (pinfunction "1_1") (pintype "passive"))
      (node (ref "R13K") (pin "1") (pinfunction "1_1") (pintype "passive"))
      (node (ref "R14K") (pin "1") (pinfunction "1_1") (pintype "passive"))
      (node (ref "R15K") (pin "1") (pinfunction "1_1") (pintype "passive"))
      (node (ref "R16K") (pin "2") (pinfunction "2_2") (pintype "passive"))
      (node (ref "R7K") (pin "2") (pinfunction "2_2") (pintype "passive"))
      (node (ref "R8K") (pin "2") (pinfunction "2_2") (pintype "passive"))
      (node (ref "Tp1K") (pin "1") (pinfunction "1_1") (pintype "passive"))
      (node (ref "U1K") (pin "21") (pinfunction "VCC_21") (pintype "passive"))
    )
    (net (code "13") (name "3V3_STB") (class "Default")
      (node (ref "C1K") (pin "1") (pinfunction "1_1") (pintype "passive"))
      (node (ref "FB1K") (pin "2") (pinfunction "2_2") (pintype "passive"))
      (node (ref "P1K") (pin "3") (pinfunction "3_3") (pintype "passive"))
      (node (ref "TP2K") (pin "1") (pinfunction "1_1") (pintype "passive"))
    )
    (net (code "14") (name "GND") (class "Default")
      (node (ref "C10K") (pin "2") (pinfunction "2_2") (pintype "passive"))
      (node (ref "C11K") (pin "2") (pinfunction "2_2") (pintype "passive"))
      (node (ref "C12K") (pin "2") (pinfunction "2_2") (pintype "passive"))
      (node (ref "C13K") (pin "2") (pinfunction "2_2") (pintype "passive"))
      (node (ref "C14K") (pin "2") (pinfunction "2_2") (pintype "passive"))
      (node (ref "C1K") (pin "2") (pinfunction "2_2") (pintype "passive"))
      (node (ref "C2K") (pin "2") (pinfunction "2_2") (pintype "passive"))
      (node (ref "C3K") (pin "2") (pinfunction "2_2") (pintype "passive"))
      (node (ref "C4K") (pin "2") (pinfunction "2_2") (pintype "passive"))
      (node (ref "C5K") (pin "1") (pinfunction "1_1") (pintype "passive"))
      (node (ref "C6K") (pin "1") (pinfunction "1_1") (pintype "passive"))
      (node (ref "C7K") (pin "2") (pinfunction "2_2") (pintype "passive"))
      (node (ref "C8K") (pin "2") (pinfunction "2_2") (pintype "passive"))
      (node (ref "C9K") (pin "2") (pinfunction "2_2") (pintype "passive"))
      (node (ref "ESD10K") (pin "1") (pinfunction "1_1") (pintype "passive"))
      (node (ref "ESD1K") (pin "1") (pinfunction "1_1") (pintype "passive"))
      (node (ref "ESD2K") (pin "1") (pinfunction "1_1") (pintype "passive"))
      (node (ref "ESD3K") (pin "1") (pinfunction "1_1") (pintype "passive"))
      (node (ref "ESD4K") (pin "1") (pinfunction "1_1") (pintype "passive"))
      (node (ref "ESD5K") (pin "1") (pinfunction "1_1") (pintype "passive"))
      (node (ref "ESD6K") (pin "1") (pinfunction "1_1") (pintype "passive"))
      (node (ref "ESD7K") (pin "1") (pinfunction "1_1") (pintype "passive"))
      (node (ref "ESD8K") (pin "1") (pinfunction "1_1") (pintype "passive"))
      (node (ref "ESD9K") (pin "1") (pinfunction "1_1") (pintype "passive"))
      (node (ref "P1K") (pin "1") (pinfunction "1_1") (pintype "passive"))
      (node (ref "P1K") (pin "10") (pinfunction "10_10") (pintype "passive"))
      (node (ref "P1K") (pin "11") (pinfunction "11_11") (pintype "passive"))
      (node (ref "P1K") (pin "2") (pinfunction "2_2") (pintype "passive"))
      (node (ref "P1K") (pin "7") (pinfunction "7_7") (pintype "passive"))
      (node (ref "Q3K") (pin "S") (pinfunction "S_S") (pintype "passive"))
      (node (ref "R10K") (pin "2") (pinfunction "2_2") (pintype "passive"))
      (node (ref "R23K") (pin "1") (pinfunction "1_1") (pintype "passive"))
      (node (ref "R24K") (pin "1") (pinfunction "1_1") (pintype "passive"))
      (node (ref "R9K") (pin "2") (pinfunction "2_2") (pintype "passive"))
      (node (ref "S1K") (pin "1") (pinfunction "1_1") (pintype "passive"))
      (node (ref "S1K") (pin "2") (pinfunction "2_2") (pintype "passive"))
      (node (ref "S2K") (pin "1") (pinfunction "1_1") (pintype "passive"))
      (node (ref "S2K") (pin "2") (pinfunction "2_2") (pintype "passive"))
      (node (ref "S3K") (pin "1") (pinfunction "1_1") (pintype "passive"))
      (node (ref "S3K") (pin "2") (pinfunction "2_2") (pintype "passive"))
      (node (ref "S4K") (pin "1") (pinfunction "1_1") (pintype "passive"))
      (node (ref "S4K") (pin "2") (pinfunction "2_2") (pintype "passive"))
      (node (ref "S5K") (pin "1") (pinfunction "1_1") (pintype "passive"))
      (node (ref "S5K") (pin "2") (pinfunction "2_2") (pintype "passive"))
      (node (ref "TP8K") (pin "1") (pinfunction "1_1") (pintype "passive"))
      (node (ref "U1K") (pin "0") (pinfunction "T_PAD_0") (pintype "passive"))
      (node (ref "U1K") (pin "9") (pinfunction "GND_9") (pintype "passive"))
    )
    (net (code "15") (name "Net-(C10K-Pad1)") (class "Default")
      (node (ref "C10K") (pin "1") (pinfunction "1_1") (pintype "passive"))
      (node (ref "R20K") (pin "2") (pinfunction "2_2") (pintype "passive"))
      (node (ref "R22K") (pin "1") (pinfunction "1_1") (pintype "passive"))
      (node (ref "R23K") (pin "2") (pinfunction "2_2") (pintype "passive"))
    )
    (net (code "16") (name "Net-(D1K-PadB)") (class "Default")
      (node (ref "D1K") (pin "B") (pinfunction "B_B") (pintype "passive"))
      (node (ref "R1K") (pin "1") (pinfunction "1_1") (pintype "passive"))
    )
    (net (code "17") (name "Net-(D1K-PadG)") (class "Default")
      (node (ref "D1K") (pin "G") (pinfunction "G_G") (pintype "passive"))
      (node (ref "R2K") (pin "1") (pinfunction "1_1") (pintype "passive"))
    )
    (net (code "18") (name "Net-(D1K-PadR)") (class "Default")
      (node (ref "D1K") (pin "R") (pinfunction "R_R") (pintype "passive"))
      (node (ref "R3K") (pin "1") (pinfunction "1_1") (pintype "passive"))
    )
    (net (code "19") (name "Net-(D2K-PadB)") (class "Default")
      (node (ref "D2K") (pin "B") (pinfunction "B_B") (pintype "passive"))
      (node (ref "R6K") (pin "1") (pinfunction "1_1") (pintype "passive"))
    )
    (net (code "20") (name "Net-(D2K-PadG)") (class "Default")
      (node (ref "D2K") (pin "G") (pinfunction "G_G") (pintype "passive"))
      (node (ref "R5K") (pin "1") (pinfunction "1_1") (pintype "passive"))
    )
    (net (code "21") (name "Net-(D2K-PadR)") (class "Default")
      (node (ref "D2K") (pin "R") (pinfunction "R_R") (pintype "passive"))
      (node (ref "R4K") (pin "1") (pinfunction "1_1") (pintype "passive"))
    )
    (net (code "22") (name "Net-(Q1K-PadD)") (class "Default")
      (node (ref "Q1K") (pin "D") (pinfunction "D_D") (pintype "passive"))
      (node (ref "R20K") (pin "1") (pinfunction "1_1") (pintype "passive"))
    )
    (net (code "23") (name "Net-(Q1K-PadG)") (class "Default")
      (node (ref "Q1K") (pin "G") (pinfunction "G_G") (pintype "passive"))
      (node (ref "R17K") (pin "2") (pinfunction "2_2") (pintype "passive"))
    )
    (net (code "24") (name "Net-(Q1K-PadS)") (class "Default")
      (node (ref "Q1K") (pin "S") (pinfunction "S_S") (pintype "passive"))
      (node (ref "R15K") (pin "2") (pinfunction "2_2") (pintype "passive"))
    )
    (net (code "25") (name "Net-(Q2K-PadD)") (class "Default")
      (node (ref "Q2K") (pin "D") (pinfunction "D_D") (pintype "passive"))
      (node (ref "Q4K") (pin "S") (pinfunction "S_S") (pintype "passive"))
    )
    (net (code "26") (name "Net-(Q2K-PadG)") (class "Default")
      (node (ref "Q2K") (pin "G") (pinfunction "G_G") (pintype "passive"))
      (node (ref "R18K") (pin "2") (pinfunction "2_2") (pintype "passive"))
    )
    (net (code "27") (name "Net-(Q2K-PadS)") (class "Default")
      (node (ref "Q2K") (pin "S") (pinfunction "S_S") (pintype "passive"))
      (node (ref "R16K") (pin "1") (pinfunction "1_1") (pintype "passive"))
      (node (ref "R17K") (pin "1") (pinfunction "1_1") (pintype "passive"))
    )
    (net (code "28") (name "Net-(Q3K-PadD)") (class "Default")
      (node (ref "Q3K") (pin "D") (pinfunction "D_D") (pintype "passive"))
      (node (ref "R19K") (pin "2") (pinfunction "2_2") (pintype "passive"))
    )
    (net (code "29") (name "Net-(Q3K-PadG)") (class "Default")
      (node (ref "Q3K") (pin "G") (pinfunction "G_G") (pintype "passive"))
      (node (ref "R22K") (pin "2") (pinfunction "2_2") (pintype "passive"))
    )
    (net (code "30") (name "Net-(Q4K-PadD)") (class "Default")
      (node (ref "Q4K") (pin "D") (pinfunction "D_D") (pintype "passive"))
      (node (ref "R24K") (pin "2") (pinfunction "2_2") (pintype "passive"))
    )
    (net (code "31") (name "Net-(Q4K-PadG)") (class "Default")
      (node (ref "Q4K") (pin "G") (pinfunction "G_G") (pintype "passive"))
      (node (ref "R21K") (pin "2") (pinfunction "2_2") (pintype "passive"))
    )
    (net (code "32") (name "Net-(U1K-AD0)") (class "Default")
      (node (ref "R7K") (pin "1") (pinfunction "1_1") (pintype "passive"))
      (node (ref "R9K") (pin "1") (pinfunction "1_1") (pintype "passive"))
      (node (ref "U1K") (pin "18") (pinfunction "AD0_18") (pintype "passive"))
    )
    (net (code "33") (name "Net-(U1K-AD1)") (class "Default")
      (node (ref "R10K") (pin "1") (pinfunction "1_1") (pintype "passive"))
      (node (ref "R8K") (pin "1") (pinfunction "1_1") (pintype "passive"))
      (node (ref "U1K") (pin "24") (pinfunction "AD1_24") (pintype "passive"))
    )
    (net (code "34") (name "Net-(U1K-P0_2)") (class "Default")
      (node (ref "C11K") (pin "1") (pinfunction "1_1") (pintype "passive"))
      (node (ref "R25K") (pin "1") (pinfunction "1_1") (pintype "passive"))
      (node (ref "U1K") (pin "7") (pinfunction "P0_2_7") (pintype "passive"))
    )
    (net (code "35") (name "Net-(U1K-P0_3)") (class "Default")
      (node (ref "C12K") (pin "1") (pinfunction "1_1") (pintype "passive"))
      (node (ref "R26K") (pin "1") (pinfunction "1_1") (pintype "passive"))
      (node (ref "U1K") (pin "8") (pinfunction "P0_3_8") (pintype "passive"))
    )
    (net (code "36") (name "Net-(U1K-P0_4)") (class "Default")
      (node (ref "C13K") (pin "1") (pinfunction "1_1") (pintype "passive"))
      (node (ref "R27K") (pin "1") (pinfunction "1_1") (pintype "passive"))
      (node (ref "U1K") (pin "10") (pinfunction "P0_4_10") (pintype "passive"))
    )
    (net (code "37") (name "Net-(U1K-P0_5)") (class "Default")
      (node (ref "C14K") (pin "1") (pinfunction "1_1") (pintype "passive"))
      (node (ref "R28K") (pin "1") (pinfunction "1_1") (pintype "passive"))
      (node (ref "U1K") (pin "11") (pinfunction "P0_5_11") (pintype "passive"))
    )
    (net (code "38") (name "Net-(U1K-P1_0)") (class "Default")
      (node (ref "R4K") (pin "2") (pinfunction "2_2") (pintype "passive"))
      (node (ref "U1K") (pin "1") (pinfunction "P1_0_1") (pintype "passive"))
    )
    (net (code "39") (name "Net-(U1K-P1_1)") (class "Default")
      (node (ref "R5K") (pin "2") (pinfunction "2_2") (pintype "passive"))
      (node (ref "U1K") (pin "2") (pinfunction "P1_1_2") (pintype "passive"))
    )
    (net (code "40") (name "Net-(U1K-P1_2)") (class "Default")
      (node (ref "R6K") (pin "2") (pinfunction "2_2") (pintype "passive"))
      (node (ref "U1K") (pin "3") (pinfunction "P1_2_3") (pintype "passive"))
    )
    (net (code "41") (name "Net-(U1K-P1_4)") (class "Default")
      (node (ref "R1K") (pin "2") (pinfunction "2_2") (pintype "passive"))
      (node (ref "U1K") (pin "14") (pinfunction "P1_4_14") (pintype "passive"))
    )
    (net (code "42") (name "Net-(U1K-P1_5)") (class "Default")
      (node (ref "R2K") (pin "2") (pinfunction "2_2") (pintype "passive"))
      (node (ref "U1K") (pin "15") (pinfunction "P1_5_15") (pintype "passive"))
    )
    (net (code "43") (name "Net-(U1K-P1_6)") (class "Default")
      (node (ref "R3K") (pin "2") (pinfunction "2_2") (pintype "passive"))
      (node (ref "U1K") (pin "16") (pinfunction "P1_6_16") (pintype "passive"))
    )
    (net (code "44") (name "unconnected-(MK_T1K-PadMK_B)") (class "Default")
      (node (ref "MK_T1K") (pin "MK_B") (pinfunction "MK_B_MK_B") (pintype "passive"))
    )
    (net (code "45") (name "unconnected-(MK_T1K-PadMK_T)") (class "Default")
      (node (ref "MK_T1K") (pin "MK_T") (pinfunction "MK_T_MK_T") (pintype "passive"))
    )
    (net (code "46") (name "unconnected-(MK_T2K-PadMK_B)") (class "Default")
      (node (ref "MK_T2K") (pin "MK_B") (pinfunction "MK_B_MK_B") (pintype "passive"))
    )
    (net (code "47") (name "unconnected-(MK_T2K-PadMK_T)") (class "Default")
      (node (ref "MK_T2K") (pin "MK_T") (pinfunction "MK_T_MK_T") (pintype "passive"))
    )
    (net (code "48") (name "unconnected-(U1K-P0_0-Pad5)") (class "Default")
      (node (ref "U1K") (pin "5") (pinfunction "P0_0_5") (pintype "passive+no_connect"))
    )
    (net (code "49") (name "unconnected-(U1K-P0_1-Pad6)") (class "Default")
      (node (ref "U1K") (pin "6") (pinfunction "P0_1_6") (pintype "passive+no_connect"))
    )
    (net (code "50") (name "unconnected-(U1K-P0_6-Pad12)") (class "Default")
      (node (ref "U1K") (pin "12") (pinfunction "P0_6_12") (pintype "passive+no_connect"))
    )
    (net (code "51") (name "unconnected-(U1K-P0_7-Pad13)") (class "Default")
      (node (ref "U1K") (pin "13") (pinfunction "P0_7_13") (pintype "passive+no_connect"))
    )
    (net (code "52") (name "unconnected-(U1K-P1_3-Pad4)") (class "Default")
      (node (ref "U1K") (pin "4") (pinfunction "P1_3_4") (pintype "passive+no_connect"))
    )
    (net (code "53") (name "unconnected-(U1K-P1_7-Pad17)") (class "Default")
      (node (ref "U1K") (pin "17") (pinfunction "P1_7_17") (pintype "passive+no_connect"))
    )
  )
)
